# 1_P1_schdoc.net
KiCad netlist of a schematic drawn in Altium Designer
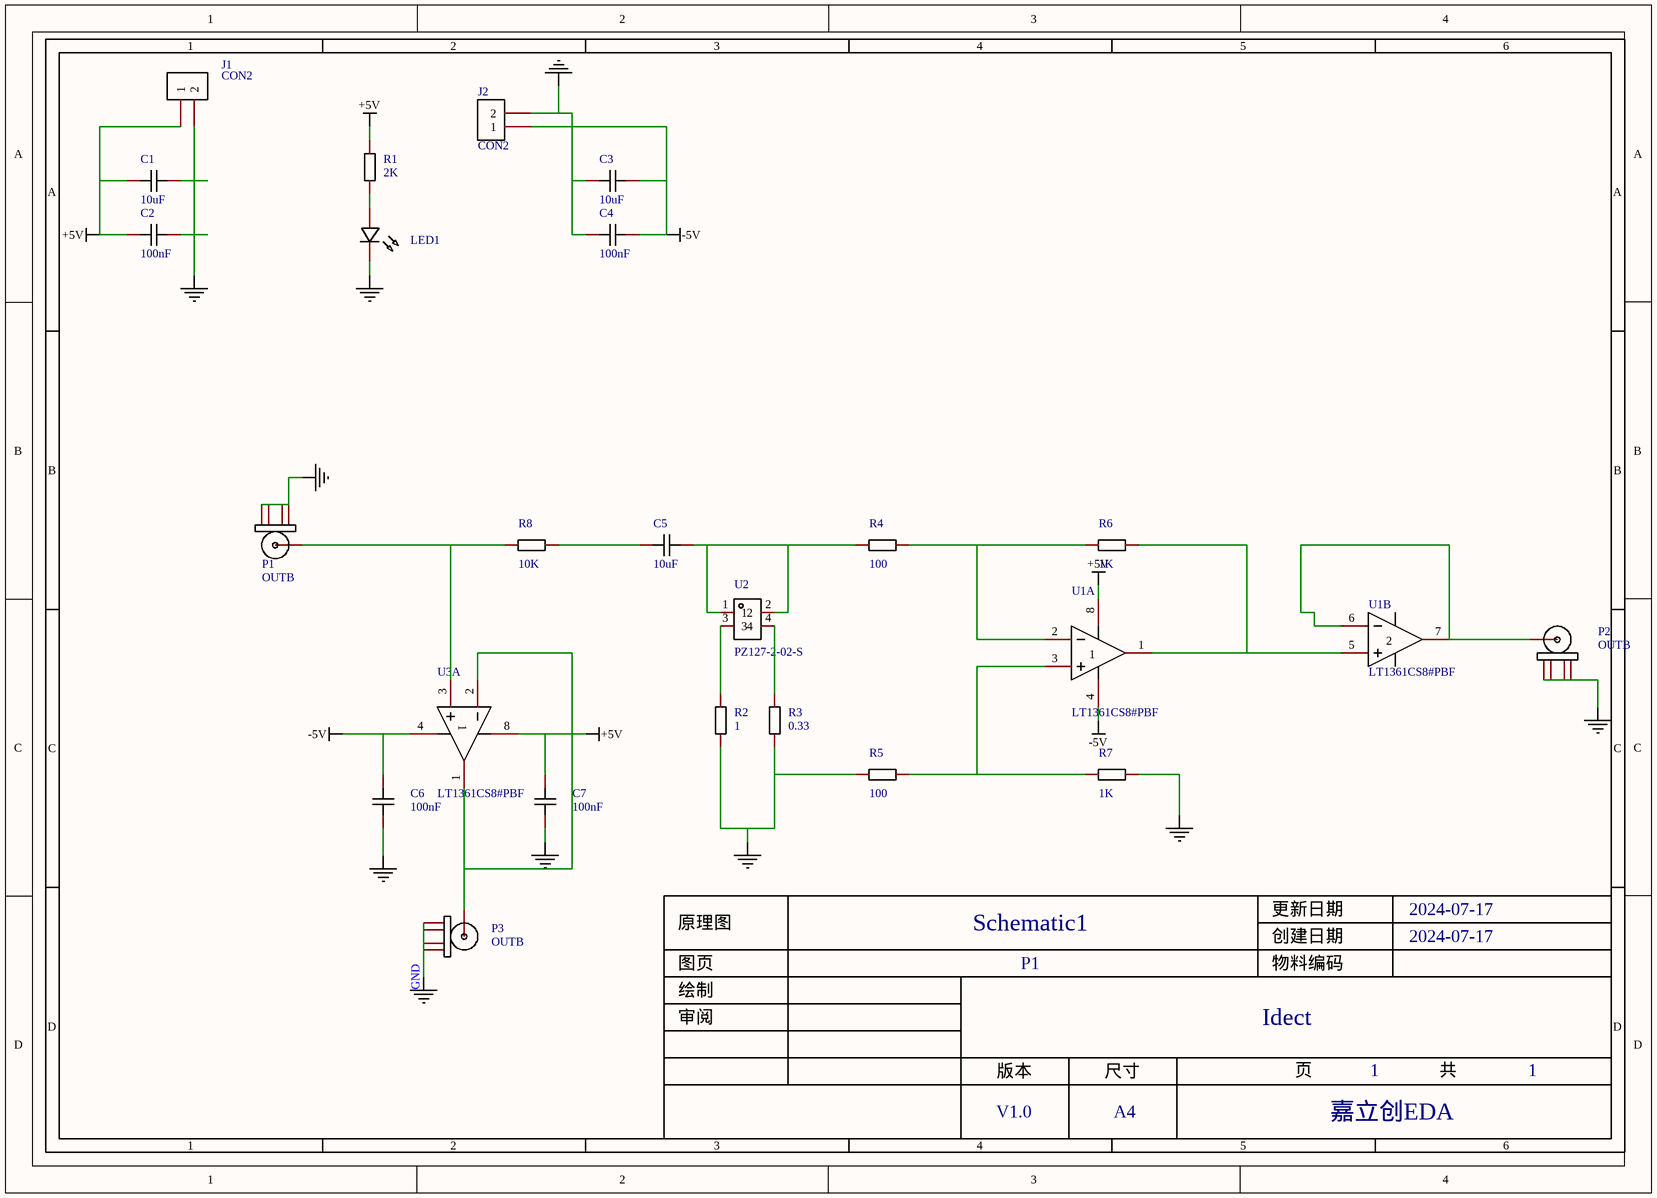
[diagram p0: 1_P1.schdoc.schdoc]

(export (version "E")
  (design (tool "Eeschema 10.0.6"))
  (components
    (comp (ref "C1")
      (value "10uF")
      (fields (field (name "NAME") "10uF"))
      (libsource (lib "altium-import") (part "root_0_CAP_0805_"))
    )
    (comp (ref "C2")
      (value "100nF")
      (fields (field (name "NAME") "100nF"))
      (libsource (lib "altium-import") (part "root_0_CAP_0805_"))
    )
    (comp (ref "C3")
      (value "10uF")
      (fields (field (name "NAME") "10uF"))
      (libsource (lib "altium-import") (part "root_0_CAP_0805_"))
    )
    (comp (ref "C4")
      (value "100nF")
      (fields (field (name "NAME") "100nF"))
      (libsource (lib "altium-import") (part "root_0_CAP_0805_"))
    )
    (comp (ref "C5")
      (value "10uF")
      (fields (field (name "NAME") "10uF"))
      (libsource (lib "altium-import") (part "root_0_CAP_0805_"))
    )
    (comp (ref "C6")
      (value "100nF")
      (fields (field (name "NAME") "100nF"))
      (libsource (lib "altium-import") (part "root_1_CAP_0805_"))
    )
    (comp (ref "C7")
      (value "100nF")
      (fields (field (name "NAME") "100nF"))
      (libsource (lib "altium-import") (part "root_1_CAP_0805_"))
    )
    (comp (ref "J1")
      (value "CON2")
      (fields (field (name "NAME") "CON2"))
      (libsource (lib "altium-import") (part "root_0_CON2_"))
    )
    (comp (ref "J2")
      (value "CON2")
      (fields (field (name "NAME") "CON2"))
      (libsource (lib "altium-import") (part "root_1_CON2_"))
    )
    (comp (ref "LED1") (value "LED_0805-R") (libsource (lib "altium-import") (part "root_3_LED_0805-R_")))
    (comp (ref "P1")
      (value "OUTB")
      (fields (field (name "NAME") "OUTB"))
      (libsource (lib "altium-import") (part "root_2_BNC_"))
    )
    (comp (ref "P2")
      (value "OUTB")
      (fields (field (name "NAME") "OUTB"))
      (libsource (lib "altium-import") (part "root_0_BNC_"))
    )
    (comp (ref "P3")
      (value "OUTB")
      (fields (field (name "NAME") "OUTB"))
      (libsource (lib "altium-import") (part "root_3_BNC_"))
    )
    (comp (ref "R1")
      (value "2K")
      (fields (field (name "NAME") "2K"))
      (libsource (lib "altium-import") (part "root_3_Res_0805_"))
    )
    (comp (ref "R2")
      (value "1")
      (fields (field (name "NAME") "1"))
      (libsource (lib "altium-import") (part "root_1_Res_0805_"))
    )
    (comp (ref "R3")
      (value "0.33")
      (fields (field (name "NAME") "0.33"))
      (libsource (lib "altium-import") (part "root_1_Res_0805_"))
    )
    (comp (ref "R4")
      (value "100")
      (fields (field (name "NAME") "100"))
      (libsource (lib "altium-import") (part "root_0_Res_0805_"))
    )
    (comp (ref "R5")
      (value "100")
      (fields (field (name "NAME") "100"))
      (libsource (lib "altium-import") (part "root_0_Res_0805_"))
    )
    (comp (ref "R6")
      (value "1K")
      (fields (field (name "NAME") "1K"))
      (libsource (lib "altium-import") (part "root_0_Res_0805_"))
    )
    (comp (ref "R7")
      (value "1K")
      (fields (field (name "NAME") "1K"))
      (libsource (lib "altium-import") (part "root_0_Res_0805_"))
    )
    (comp (ref "R8")
      (value "10K")
      (fields (field (name "NAME") "10K"))
      (libsource (lib "altium-import") (part "root_0_Res_1218_"))
    )
    (comp (ref "U1")
      (value "LT1361CS8#PBF")
      (description "放大器数:双路;增益带宽积(GBP):50MHz;输入偏置电流(Ib):300nA;压摆率(SR):800V/us;带宽(-3db):-;")
      (fields (field (name "NAME") "LT1361CS8#PBF") (field (name "MANUFACTURER") "ADI(亚德诺)"))
      (libsource (lib "altium-import") (part "root_0_LT1361CS8#PBF_"))
    )
    (comp (ref "U2")
      (value "PZ127-2-02-S")
      (fields (field (name "NAME") "PZ127-2-02-S") (field (name "MANUFACTURER") "HCTL(华灿天禄)"))
      (libsource (lib "altium-import") (part "root_0_PZ127-2-02-S_"))
    )
    (comp (ref "U3")
      (value "LT1361CS8#PBF")
      (description "放大器数:双路;增益带宽积(GBP):50MHz;输入偏置电流(Ib):300nA;压摆率(SR):800V/us;带宽(-3db):-;")
      (fields (field (name "NAME") "LT1361CS8#PBF") (field (name "MANUFACTURER") "ADI(亚德诺)"))
      (libsource (lib "altium-import") (part "root_3_LT1361CS8#PBF_"))
    )
  )
  (nets
    (net (code "1") (name "+5V") (class "Default")
      (node (ref "C1") (pin "1") (pinfunction "1_1") (pintype "passive"))
      (node (ref "C2") (pin "1") (pinfunction "1_1") (pintype "passive"))
      (node (ref "C7") (pin "2") (pinfunction "2_2") (pintype "passive"))
      (node (ref "J1") (pin "1") (pinfunction "1_1") (pintype "passive"))
      (node (ref "R1") (pin "1") (pinfunction "1_1") (pintype "passive"))
      (node (ref "U1") (pin "8") (pinfunction "V+_8") (pintype "passive"))
      (node (ref "U3") (pin "8") (pinfunction "V+_8") (pintype "passive"))
    )
    (net (code "2") (name "-5V") (class "Default")
      (node (ref "C3") (pin "2") (pinfunction "2_2") (pintype "passive"))
      (node (ref "C4") (pin "2") (pinfunction "2_2") (pintype "passive"))
      (node (ref "C6") (pin "2") (pinfunction "2_2") (pintype "passive"))
      (node (ref "J2") (pin "1") (pinfunction "1_1") (pintype "passive"))
      (node (ref "U1") (pin "4") (pinfunction "V-_4") (pintype "passive"))
      (node (ref "U3") (pin "4") (pinfunction "V-_4") (pintype "passive"))
    )
    (net (code "3") (name "GND") (class "Default")
      (node (ref "C1") (pin "2") (pinfunction "2_2") (pintype "passive"))
      (node (ref "C2") (pin "2") (pinfunction "2_2") (pintype "passive"))
      (node (ref "C3") (pin "1") (pinfunction "1_1") (pintype "passive"))
      (node (ref "C4") (pin "1") (pinfunction "1_1") (pintype "passive"))
      (node (ref "C6") (pin "1") (pinfunction "1_1") (pintype "passive"))
      (node (ref "C7") (pin "1") (pinfunction "1_1") (pintype "passive"))
      (node (ref "J1") (pin "2") (pinfunction "2_2") (pintype "passive"))
      (node (ref "J2") (pin "2") (pinfunction "2_2") (pintype "passive"))
      (node (ref "LED1") (pin "1") (pinfunction "C_1") (pintype "passive"))
      (node (ref "P1") (pin "2") (pinfunction "GND_2") (pintype "passive"))
      (node (ref "P1") (pin "3") (pinfunction "GND_3") (pintype "passive"))
      (node (ref "P1") (pin "4") (pinfunction "GND_4") (pintype "passive"))
      (node (ref "P1") (pin "5") (pinfunction "GND_5") (pintype "passive"))
      (node (ref "P2") (pin "2") (pinfunction "GND_2") (pintype "passive"))
      (node (ref "P2") (pin "3") (pinfunction "GND_3") (pintype "passive"))
      (node (ref "P2") (pin "4") (pinfunction "GND_4") (pintype "passive"))
      (node (ref "P2") (pin "5") (pinfunction "GND_5") (pintype "passive"))
      (node (ref "P3") (pin "2") (pinfunction "GND_2") (pintype "passive"))
      (node (ref "P3") (pin "3") (pinfunction "GND_3") (pintype "passive"))
      (node (ref "P3") (pin "4") (pinfunction "GND_4") (pintype "passive"))
      (node (ref "P3") (pin "5") (pinfunction "GND_5") (pintype "passive"))
      (node (ref "R2") (pin "1") (pinfunction "1_1") (pintype "passive"))
      (node (ref "R3") (pin "1") (pinfunction "1_1") (pintype "passive"))
      (node (ref "R5") (pin "1") (pinfunction "1_1") (pintype "passive"))
      (node (ref "R7") (pin "2") (pinfunction "2_2") (pintype "passive"))
    )
    (net (code "4") (name "Net-(C5-Pad1)") (class "Default")
      (node (ref "C5") (pin "1") (pinfunction "1_1") (pintype "passive"))
      (node (ref "R8") (pin "2") (pinfunction "2_2") (pintype "passive"))
    )
    (net (code "5") (name "Net-(C5-Pad2)") (class "Default")
      (node (ref "C5") (pin "2") (pinfunction "2_2") (pintype "passive"))
      (node (ref "R4") (pin "1") (pinfunction "1_1") (pintype "passive"))
      (node (ref "U2") (pin "1") (pinfunction "1_1") (pintype "passive"))
      (node (ref "U2") (pin "2") (pinfunction "2_2") (pintype "passive"))
    )
    (net (code "6") (name "Net-(LED1-A)") (class "Default")
      (node (ref "LED1") (pin "2") (pinfunction "A_2") (pintype "passive"))
      (node (ref "R1") (pin "2") (pinfunction "2_2") (pintype "passive"))
    )
    (net (code "7") (name "Net-(P1-X)") (class "Default")
      (node (ref "P1") (pin "1") (pinfunction "X_1") (pintype "passive"))
      (node (ref "R8") (pin "1") (pinfunction "1_1") (pintype "passive"))
      (node (ref "U3") (pin "3") (pinfunction "INA+_3") (pintype "passive"))
    )
    (net (code "8") (name "Net-(P2-X)") (class "Default")
      (node (ref "P2") (pin "1") (pinfunction "X_1") (pintype "passive"))
      (node (ref "U1") (pin "6") (pinfunction "INB-_6") (pintype "passive"))
      (node (ref "U1") (pin "7") (pinfunction "OUTB_7") (pintype "passive"))
    )
    (net (code "9") (name "Net-(P3-X)") (class "Default")
      (node (ref "P3") (pin "1") (pinfunction "X_1") (pintype "passive"))
      (node (ref "U3") (pin "1") (pinfunction "OUTA_1") (pintype "passive"))
      (node (ref "U3") (pin "2") (pinfunction "INA-_2") (pintype "passive"))
    )
    (net (code "10") (name "Net-(R2-Pad2)") (class "Default")
      (node (ref "R2") (pin "2") (pinfunction "2_2") (pintype "passive"))
      (node (ref "U2") (pin "3") (pinfunction "3_3") (pintype "passive"))
    )
    (net (code "11") (name "Net-(R3-Pad2)") (class "Default")
      (node (ref "R3") (pin "2") (pinfunction "2_2") (pintype "passive"))
      (node (ref "U2") (pin "4") (pinfunction "4_4") (pintype "passive"))
    )
    (net (code "12") (name "Net-(U1A-INA+)") (class "Default")
      (node (ref "R5") (pin "2") (pinfunction "2_2") (pintype "passive"))
      (node (ref "R7") (pin "1") (pinfunction "1_1") (pintype "passive"))
      (node (ref "U1") (pin "3") (pinfunction "INA+_3") (pintype "passive"))
    )
    (net (code "13") (name "Net-(U1A-INA-)") (class "Default")
      (node (ref "R4") (pin "2") (pinfunction "2_2") (pintype "passive"))
      (node (ref "R6") (pin "1") (pinfunction "1_1") (pintype "passive"))
      (node (ref "U1") (pin "2") (pinfunction "INA-_2") (pintype "passive"))
    )
    (net (code "14") (name "Net-(U1A-OUTA)") (class "Default")
      (node (ref "R6") (pin "2") (pinfunction "2_2") (pintype "passive"))
      (node (ref "U1") (pin "1") (pinfunction "OUTA_1") (pintype "passive"))
      (node (ref "U1") (pin "5") (pinfunction "INB+_5") (pintype "passive"))
    )
  )
)
